# FeatherUSBSerial.net
KiCad netlist of a schematic drawn in EAGLE
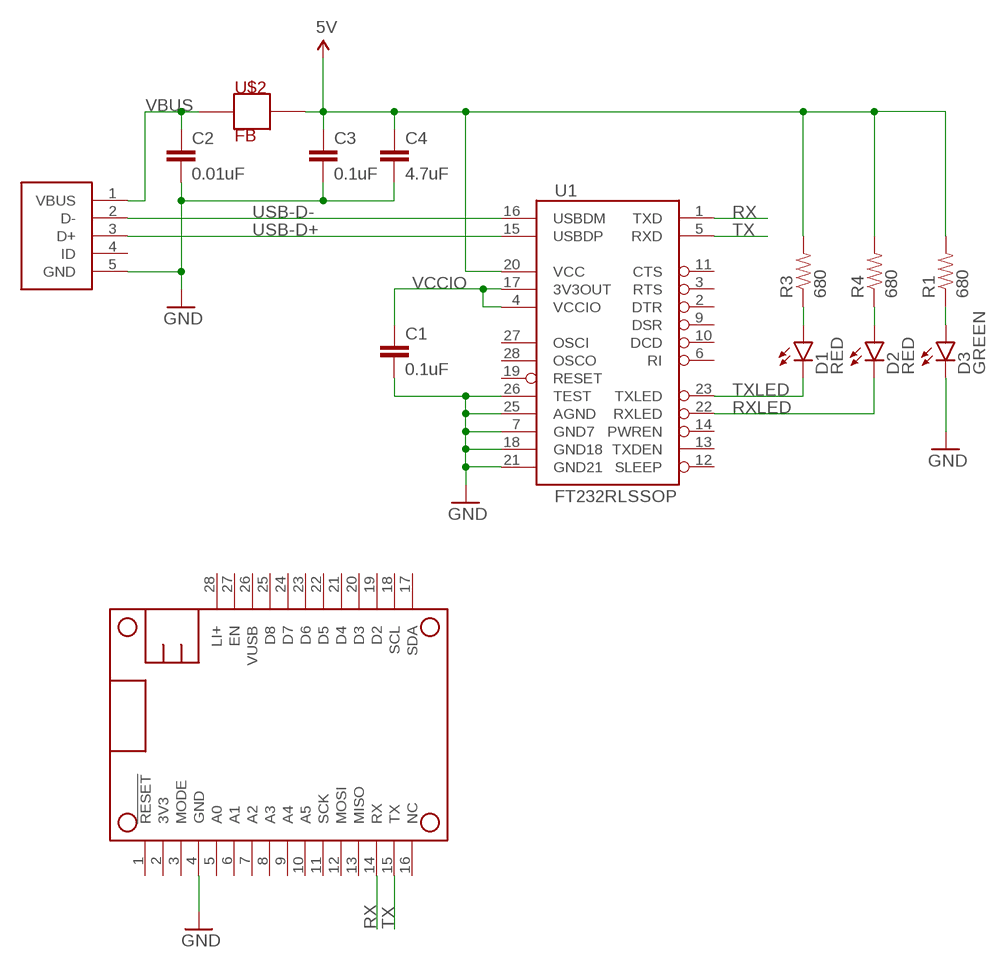
[diagram p0: schematic, sheet 1]

(export (version "E")
  (design (tool "Eeschema 10.0.6"))
  (components
    (comp (ref "C1")
      (value "0.1uF")
      (footprint "eagle-import:0603-CAP")
      (libsource (lib "eagle-import") (part "CAP-0.1UF-0603"))
    )
    (comp (ref "C2")
      (value "0.01uF")
      (footprint "eagle-import:0603-CAP")
      (libsource (lib "eagle-import") (part "CAP-0.01UF-0603"))
    )
    (comp (ref "C3")
      (value "0.1uF")
      (footprint "eagle-import:0603-CAP")
      (libsource (lib "eagle-import") (part "CAP-0.1UF-0603"))
    )
    (comp (ref "C4")
      (value "4.7uF")
      (footprint "eagle-import:0603-CAP")
      (libsource (lib "eagle-import") (part "CAP-4.7UF-0603"))
    )
    (comp (ref "D1")
      (value "RED")
      (footprint "eagle-import:LED-0603")
      (libsource (lib "eagle-import") (part "LED-RED"))
    )
    (comp (ref "D2")
      (value "RED")
      (footprint "eagle-import:LED-0603")
      (libsource (lib "eagle-import") (part "LED-RED"))
    )
    (comp (ref "D3")
      (value "GREEN")
      (footprint "eagle-import:LED-0603")
      (libsource (lib "eagle-import") (part "LED-GREEN0603"))
    )
    (comp (ref "MS1")
      (value "FEATHERWING_NODIM")
      (footprint "eagle-import:FEATHERWING_NODIM")
      (libsource (lib "eagle-import") (part "FEATHERWING_NODIM"))
    )
    (comp (ref "R1")
      (value "680")
      (footprint "eagle-import:0805")
      (libsource (lib "eagle-import") (part "RES-680-0805"))
    )
    (comp (ref "R3")
      (value "680")
      (footprint "eagle-import:0805")
      (libsource (lib "eagle-import") (part "RES-680-0805"))
    )
    (comp (ref "R4")
      (value "680")
      (footprint "eagle-import:0805")
      (libsource (lib "eagle-import") (part "RES-680-0805"))
    )
    (comp (ref "U$1")
      (value "USB-MICRO-B-SOCKET-AMPHENOL")
      (footprint "eagle-import:USB-B-SMT-AMPHENOL")
      (libsource (lib "eagle-import") (part "USB-MICRO-B-SOCKET-AMPHENOL"))
    )
    (comp (ref "U$2")
      (value "FB")
      (footprint "eagle-import:0805")
      (libsource (lib "eagle-import") (part "FERRITE-BEAD-MI0805K400R-10"))
    )
    (comp (ref "U1")
      (value "FT232RLSSOP")
      (footprint "eagle-import:SSOP28DB")
      (libsource (lib "eagle-import") (part "FT232RLSSOP"))
    )
  )
  (nets
    (net (code "1") (name "/3V3") (class "Default")
      (node (ref "MS1") (pin "2") (pinfunction "3V3_2") (pintype "power_in"))
    )
    (net (code "2") (name "/LI+") (class "Default")
      (node (ref "MS1") (pin "28") (pinfunction "LI+_28") (pintype "power_in"))
    )
    (net (code "3") (name "/RX") (class "Default")
      (node (ref "MS1") (pin "14") (pinfunction "RX_14") (pintype "bidirectional"))
      (node (ref "U1") (pin "1") (pinfunction "TXD_1") (pintype "output"))
    )
    (net (code "4") (name "/RXLED") (class "Default")
      (node (ref "D2") (pin "C") (pinfunction "C_C") (pintype "passive"))
      (node (ref "U1") (pin "22") (pinfunction "RXLED_22") (pintype "input"))
    )
    (net (code "5") (name "/TX") (class "Default")
      (node (ref "MS1") (pin "15") (pinfunction "TX_15") (pintype "bidirectional"))
      (node (ref "U1") (pin "5") (pinfunction "RXD_5") (pintype "input"))
    )
    (net (code "6") (name "/TXLED") (class "Default")
      (node (ref "D1") (pin "C") (pinfunction "C_C") (pintype "passive"))
      (node (ref "U1") (pin "23") (pinfunction "TXLED_23") (pintype "input"))
    )
    (net (code "7") (name "/USB-D+") (class "Default")
      (node (ref "U$1") (pin "3") (pinfunction "D+_3") (pintype "passive"))
      (node (ref "U1") (pin "15") (pinfunction "USBDP_15") (pintype "bidirectional"))
    )
    (net (code "8") (name "/USB-D-") (class "Default")
      (node (ref "U$1") (pin "2") (pinfunction "D-_2") (pintype "passive"))
      (node (ref "U1") (pin "16") (pinfunction "USBDM_16") (pintype "bidirectional"))
    )
    (net (code "9") (name "/VBUS") (class "Default")
      (node (ref "C2") (pin "1") (pinfunction "1_1") (pintype "passive"))
      (node (ref "U$1") (pin "1") (pinfunction "VBUS_1") (pintype "passive"))
      (node (ref "U$2") (pin "1") (pinfunction "1_1") (pintype "passive"))
    )
    (net (code "10") (name "/VCCIO") (class "Default")
      (node (ref "C1") (pin "1") (pinfunction "1_1") (pintype "passive"))
      (node (ref "U1") (pin "17") (pinfunction "3V3OUT_17") (pintype "output"))
      (node (ref "U1") (pin "4") (pinfunction "VCCIO_4") (pintype "power_in"))
    )
    (net (code "11") (name "/VUSB") (class "Default")
      (node (ref "MS1") (pin "26") (pinfunction "VUSB_26") (pintype "power_in"))
    )
    (net (code "12") (name "5V") (class "Default")
      (node (ref "C3") (pin "1") (pinfunction "1_1") (pintype "passive"))
      (node (ref "C4") (pin "1") (pinfunction "1_1") (pintype "passive"))
      (node (ref "R1") (pin "2") (pinfunction "2_2") (pintype "passive"))
      (node (ref "R3") (pin "2") (pinfunction "2_2") (pintype "passive"))
      (node (ref "R4") (pin "2") (pinfunction "2_2") (pintype "passive"))
      (node (ref "U$2") (pin "2") (pinfunction "2_2") (pintype "passive"))
      (node (ref "U1") (pin "20") (pinfunction "VCC_20") (pintype "power_in"))
    )
    (net (code "13") (name "GND") (class "Default")
      (node (ref "C1") (pin "2") (pinfunction "2_2") (pintype "passive"))
      (node (ref "C2") (pin "2") (pinfunction "2_2") (pintype "passive"))
      (node (ref "C3") (pin "2") (pinfunction "2_2") (pintype "passive"))
      (node (ref "C4") (pin "2") (pinfunction "2_2") (pintype "passive"))
      (node (ref "D3") (pin "C") (pinfunction "C_C") (pintype "passive"))
      (node (ref "MS1") (pin "4") (pinfunction "GND_4") (pintype "power_in"))
      (node (ref "U$1") (pin "5") (pinfunction "GND_5") (pintype "passive"))
      (node (ref "U1") (pin "18") (pinfunction "GND18_18") (pintype "power_in"))
      (node (ref "U1") (pin "21") (pinfunction "GND21_21") (pintype "power_in"))
      (node (ref "U1") (pin "25") (pinfunction "AGND_25") (pintype "power_in"))
      (node (ref "U1") (pin "26") (pinfunction "TEST_26") (pintype "input"))
      (node (ref "U1") (pin "7") (pinfunction "GND7_7") (pintype "power_in"))
    )
    (net (code "14") (name "Net-(D1-PadA)") (class "Default")
      (node (ref "D1") (pin "A") (pinfunction "A_A") (pintype "passive"))
      (node (ref "R3") (pin "1") (pinfunction "1_1") (pintype "passive"))
    )
    (net (code "15") (name "Net-(D2-PadA)") (class "Default")
      (node (ref "D2") (pin "A") (pinfunction "A_A") (pintype "passive"))
      (node (ref "R4") (pin "1") (pinfunction "1_1") (pintype "passive"))
    )
    (net (code "16") (name "Net-(D3-PadA)") (class "Default")
      (node (ref "D3") (pin "A") (pinfunction "A_A") (pintype "passive"))
      (node (ref "R1") (pin "1") (pinfunction "1_1") (pintype "passive"))
    )
    (net (code "17") (name "unconnected-(MS1-A0-Pad5)") (class "Default")
      (node (ref "MS1") (pin "5") (pinfunction "A0_5") (pintype "bidirectional"))
    )
    (net (code "18") (name "unconnected-(MS1-A1-Pad6)") (class "Default")
      (node (ref "MS1") (pin "6") (pinfunction "A1_6") (pintype "bidirectional"))
    )
    (net (code "19") (name "unconnected-(MS1-A2-Pad7)") (class "Default")
      (node (ref "MS1") (pin "7") (pinfunction "A2_7") (pintype "bidirectional"))
    )
    (net (code "20") (name "unconnected-(MS1-A3-Pad8)") (class "Default")
      (node (ref "MS1") (pin "8") (pinfunction "A3_8") (pintype "bidirectional"))
    )
    (net (code "21") (name "unconnected-(MS1-A4-Pad9)") (class "Default")
      (node (ref "MS1") (pin "9") (pinfunction "A4_9") (pintype "bidirectional"))
    )
    (net (code "22") (name "unconnected-(MS1-A5-Pad10)") (class "Default")
      (node (ref "MS1") (pin "10") (pinfunction "A5_10") (pintype "bidirectional"))
    )
    (net (code "23") (name "unconnected-(MS1-D2-Pad19)") (class "Default")
      (node (ref "MS1") (pin "19") (pinfunction "D2_19") (pintype "bidirectional"))
    )
    (net (code "24") (name "unconnected-(MS1-D3-Pad20)") (class "Default")
      (node (ref "MS1") (pin "20") (pinfunction "D3_20") (pintype "bidirectional"))
    )
    (net (code "25") (name "unconnected-(MS1-D4-Pad21)") (class "Default")
      (node (ref "MS1") (pin "21") (pinfunction "D4_21") (pintype "bidirectional"))
    )
    (net (code "26") (name "unconnected-(MS1-D5-Pad22)") (class "Default")
      (node (ref "MS1") (pin "22") (pinfunction "D5_22") (pintype "bidirectional"))
    )
    (net (code "27") (name "unconnected-(MS1-D6-Pad23)") (class "Default")
      (node (ref "MS1") (pin "23") (pinfunction "D6_23") (pintype "bidirectional"))
    )
    (net (code "28") (name "unconnected-(MS1-D7-Pad24)") (class "Default")
      (node (ref "MS1") (pin "24") (pinfunction "D7_24") (pintype "bidirectional"))
    )
    (net (code "29") (name "unconnected-(MS1-D8-Pad25)") (class "Default")
      (node (ref "MS1") (pin "25") (pinfunction "D8_25") (pintype "bidirectional"))
    )
    (net (code "30") (name "unconnected-(MS1-EN-Pad27)") (class "Default")
      (node (ref "MS1") (pin "27") (pinfunction "EN_27") (pintype "passive"))
    )
    (net (code "31") (name "unconnected-(MS1-MISO-Pad13)") (class "Default")
      (node (ref "MS1") (pin "13") (pinfunction "MISO_13") (pintype "bidirectional"))
    )
    (net (code "32") (name "unconnected-(MS1-MODE-Pad3)") (class "Default")
      (node (ref "MS1") (pin "3") (pinfunction "MODE_3") (pintype "passive"))
    )
    (net (code "33") (name "unconnected-(MS1-MOSI-Pad12)") (class "Default")
      (node (ref "MS1") (pin "12") (pinfunction "MOSI_12") (pintype "bidirectional"))
    )
    (net (code "34") (name "unconnected-(MS1-NC-Pad16)") (class "Default")
      (node (ref "MS1") (pin "16") (pinfunction "NC_16") (pintype "passive"))
    )
    (net (code "35") (name "unconnected-(MS1-SCK-Pad11)") (class "Default")
      (node (ref "MS1") (pin "11") (pinfunction "SCK_11") (pintype "bidirectional"))
    )
    (net (code "36") (name "unconnected-(MS1-SCL-Pad18)") (class "Default")
      (node (ref "MS1") (pin "18") (pinfunction "SCL_18") (pintype "bidirectional"))
    )
    (net (code "37") (name "unconnected-(MS1-SDA-Pad17)") (class "Default")
      (node (ref "MS1") (pin "17") (pinfunction "SDA_17") (pintype "bidirectional"))
    )
    (net (code "38") (name "unconnected-(MS1-~{RESET}-Pad1)") (class "Default")
      (node (ref "MS1") (pin "1") (pinfunction "~{RESET}_1") (pintype "input"))
    )
    (net (code "39") (name "unconnected-(U$1-ID-Pad4)") (class "Default")
      (node (ref "U$1") (pin "4") (pinfunction "ID_4") (pintype "passive"))
    )
    (net (code "40") (name "unconnected-(U1-CTS-Pad11)") (class "Default")
      (node (ref "U1") (pin "11") (pinfunction "CTS_11") (pintype "input"))
    )
    (net (code "41") (name "unconnected-(U1-DCD-Pad10)") (class "Default")
      (node (ref "U1") (pin "10") (pinfunction "DCD_10") (pintype "input"))
    )
    (net (code "42") (name "unconnected-(U1-DSR-Pad9)") (class "Default")
      (node (ref "U1") (pin "9") (pinfunction "DSR_9") (pintype "input"))
    )
    (net (code "43") (name "unconnected-(U1-DTR-Pad2)") (class "Default")
      (node (ref "U1") (pin "2") (pinfunction "DTR_2") (pintype "output"))
    )
    (net (code "44") (name "unconnected-(U1-OSCI-Pad27)") (class "Default")
      (node (ref "U1") (pin "27") (pinfunction "OSCI_27") (pintype "input"))
    )
    (net (code "45") (name "unconnected-(U1-OSCO-Pad28)") (class "Default")
      (node (ref "U1") (pin "28") (pinfunction "OSCO_28") (pintype "output"))
    )
    (net (code "46") (name "unconnected-(U1-PWREN-Pad14)") (class "Default")
      (node (ref "U1") (pin "14") (pinfunction "PWREN_14") (pintype "input"))
    )
    (net (code "47") (name "unconnected-(U1-RESET-Pad19)") (class "Default")
      (node (ref "U1") (pin "19") (pinfunction "RESET_19") (pintype "input"))
    )
    (net (code "48") (name "unconnected-(U1-RI-Pad6)") (class "Default")
      (node (ref "U1") (pin "6") (pinfunction "RI_6") (pintype "input"))
    )
    (net (code "49") (name "unconnected-(U1-RTS-Pad3)") (class "Default")
      (node (ref "U1") (pin "3") (pinfunction "RTS_3") (pintype "output"))
    )
    (net (code "50") (name "unconnected-(U1-SLEEP-Pad12)") (class "Default")
      (node (ref "U1") (pin "12") (pinfunction "SLEEP_12") (pintype "input"))
    )
    (net (code "51") (name "unconnected-(U1-TXDEN-Pad13)") (class "Default")
      (node (ref "U1") (pin "13") (pinfunction "TXDEN_13") (pintype "input"))
    )
  )
)
